# HIGHSPEED_v0_NM.net
KiCad netlist of a schematic drawn in Altium Designer
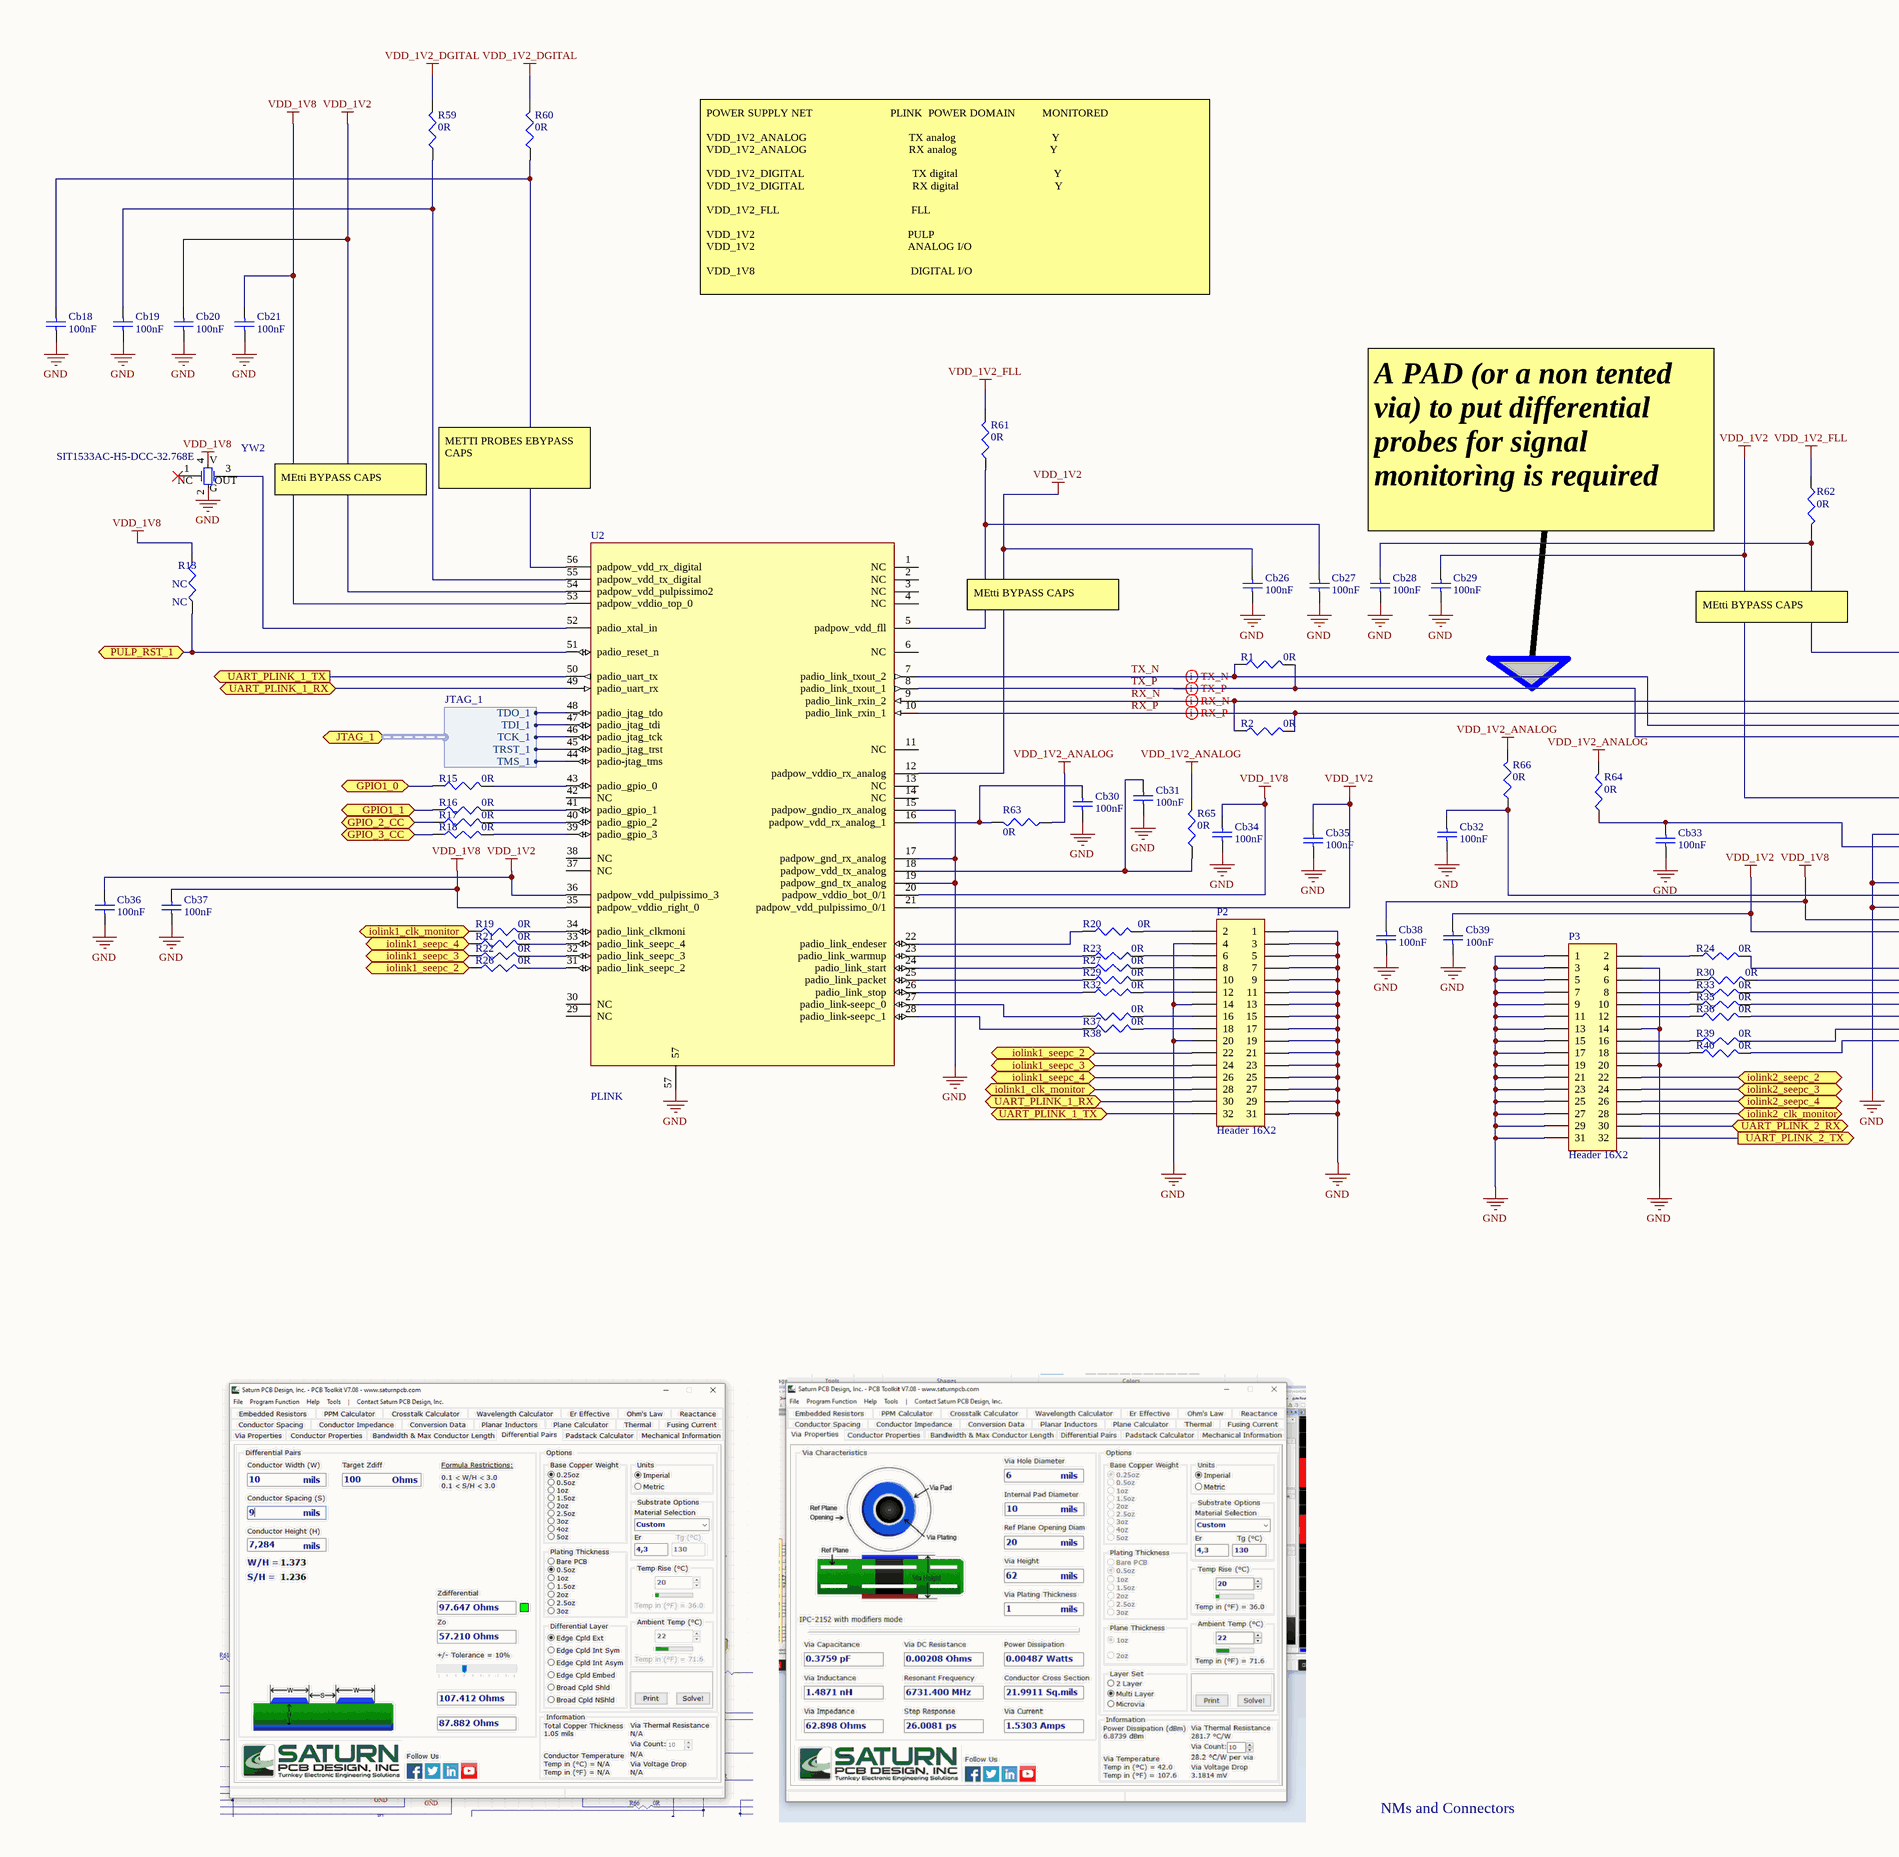
[diagram p0: HIGHSPEED_v0_NM.SchDoc, left]
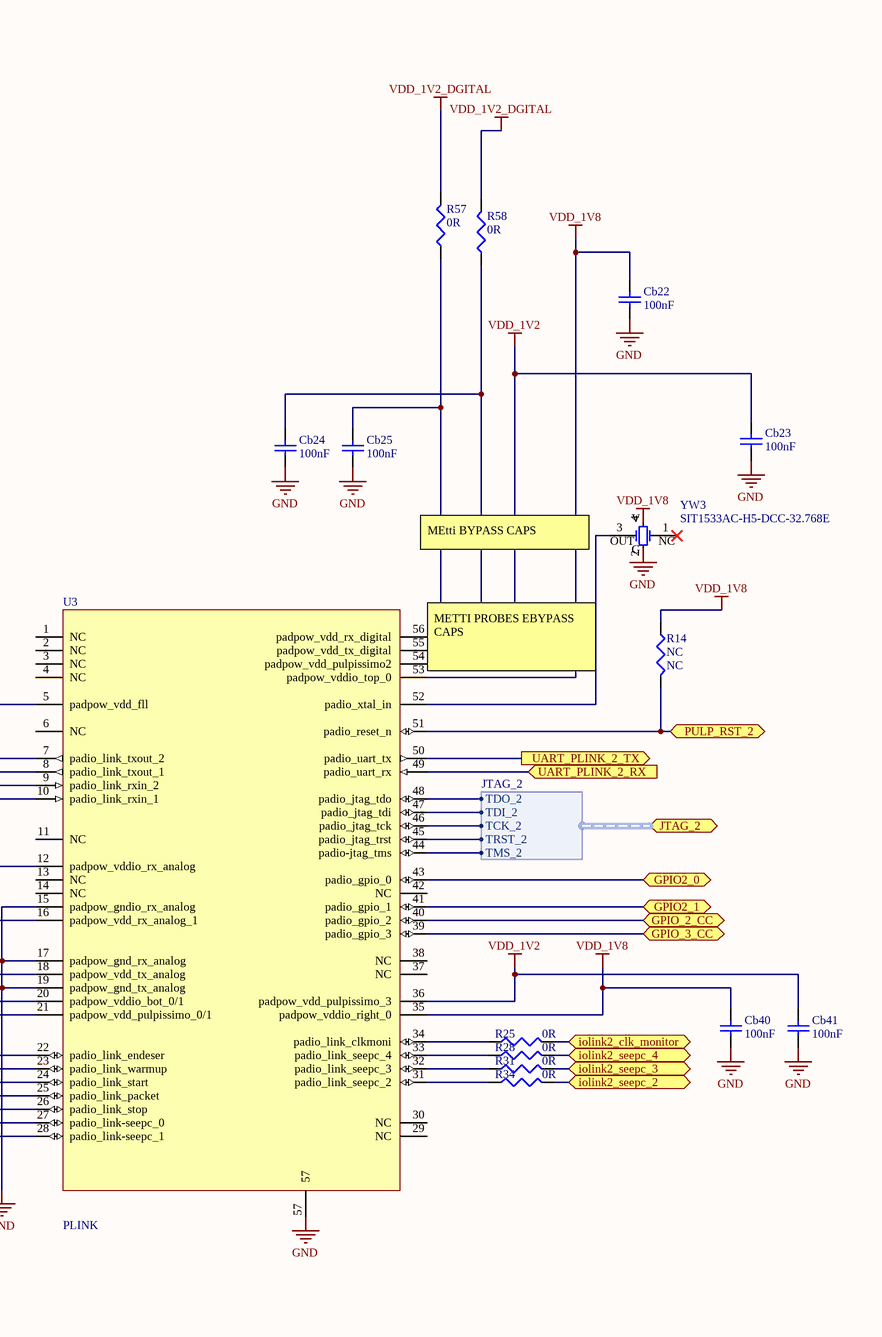
[diagram p1: HIGHSPEED_v0_NM.SchDoc, right]

(export (version "E")
  (design (tool "Eeschema 10.0.6"))
  (components
    (comp (ref "Cb18")
      (value "100nF")
      (footprint "c0603-Murata-GR")
      (description "CAP CER 22UF 10V X5R 0603")
      (fields (field (name "MANUFACTURER") "Murata") (field (name "Comment") "GRM187R61A226ME15D"))
      (libsource (lib "Custom") (part "Cap"))
    )
    (comp (ref "Cb19")
      (value "100nF")
      (footprint "c0603-Murata-GR")
      (description "CAP CER 22UF 10V X5R 0603")
      (fields (field (name "MANUFACTURER") "Murata") (field (name "Comment") "GRM187R61A226ME15D"))
      (libsource (lib "Custom") (part "Cap"))
    )
    (comp (ref "Cb20")
      (value "100nF")
      (footprint "c0603-Murata-GR")
      (description "CAP CER 22UF 10V X5R 0603")
      (fields (field (name "MANUFACTURER") "Murata") (field (name "Comment") "GRM187R61A226ME15D"))
      (libsource (lib "Custom") (part "Cap"))
    )
    (comp (ref "Cb21")
      (value "100nF")
      (footprint "c0603-Murata-GR")
      (description "CAP CER 22UF 10V X5R 0603")
      (fields (field (name "MANUFACTURER") "Murata") (field (name "Comment") "GRM187R61A226ME15D"))
      (libsource (lib "Custom") (part "Cap"))
    )
    (comp (ref "Cb22")
      (value "100nF")
      (footprint "c0603-Murata-GR")
      (description "CAP CER 22UF 10V X5R 0603")
      (fields (field (name "MANUFACTURER") "Murata") (field (name "Comment") "GRM187R61A226ME15D"))
      (libsource (lib "Custom") (part "Cap"))
    )
    (comp (ref "Cb23")
      (value "100nF")
      (footprint "c0603-Murata-GR")
      (description "CAP CER 22UF 10V X5R 0603")
      (fields (field (name "MANUFACTURER") "Murata") (field (name "Comment") "GRM187R61A226ME15D"))
      (libsource (lib "Custom") (part "Cap"))
    )
    (comp (ref "Cb24")
      (value "100nF")
      (footprint "c0603-Murata-GR")
      (description "CAP CER 22UF 10V X5R 0603")
      (fields (field (name "MANUFACTURER") "Murata") (field (name "Comment") "GRM187R61A226ME15D"))
      (libsource (lib "Custom") (part "Cap"))
    )
    (comp (ref "Cb25")
      (value "100nF")
      (footprint "c0603-Murata-GR")
      (description "CAP CER 22UF 10V X5R 0603")
      (fields (field (name "MANUFACTURER") "Murata") (field (name "Comment") "GRM187R61A226ME15D"))
      (libsource (lib "Custom") (part "Cap"))
    )
    (comp (ref "Cb26")
      (value "100nF")
      (footprint "c0603-Murata-GR")
      (description "CAP CER 22UF 10V X5R 0603")
      (fields (field (name "MANUFACTURER") "Murata") (field (name "Comment") "GRM187R61A226ME15D"))
      (libsource (lib "Custom") (part "Cap"))
    )
    (comp (ref "Cb27")
      (value "100nF")
      (footprint "c0603-Murata-GR")
      (description "CAP CER 22UF 10V X5R 0603")
      (fields (field (name "MANUFACTURER") "Murata") (field (name "Comment") "GRM187R61A226ME15D"))
      (libsource (lib "Custom") (part "Cap"))
    )
    (comp (ref "Cb28")
      (value "100nF")
      (footprint "c0603-Murata-GR")
      (description "CAP CER 22UF 10V X5R 0603")
      (fields (field (name "MANUFACTURER") "Murata") (field (name "Comment") "GRM187R61A226ME15D"))
      (libsource (lib "Custom") (part "Cap"))
    )
    (comp (ref "Cb29")
      (value "100nF")
      (footprint "c0603-Murata-GR")
      (description "CAP CER 22UF 10V X5R 0603")
      (fields (field (name "MANUFACTURER") "Murata") (field (name "Comment") "GRM187R61A226ME15D"))
      (libsource (lib "Custom") (part "Cap"))
    )
    (comp (ref "Cb30")
      (value "100nF")
      (footprint "c0603-Murata-GR")
      (description "CAP CER 22UF 10V X5R 0603")
      (fields (field (name "MANUFACTURER") "Murata") (field (name "Comment") "GRM187R61A226ME15D"))
      (libsource (lib "Custom") (part "Cap"))
    )
    (comp (ref "Cb31")
      (value "100nF")
      (footprint "c0603-Murata-GR")
      (description "CAP CER 22UF 10V X5R 0603")
      (fields (field (name "MANUFACTURER") "Murata") (field (name "Comment") "GRM187R61A226ME15D"))
      (libsource (lib "Custom") (part "Cap"))
    )
    (comp (ref "Cb32")
      (value "100nF")
      (footprint "c0603-Murata-GR")
      (description "CAP CER 22UF 10V X5R 0603")
      (fields (field (name "MANUFACTURER") "Murata") (field (name "Comment") "GRM187R61A226ME15D"))
      (libsource (lib "Custom") (part "Cap"))
    )
    (comp (ref "Cb33")
      (value "100nF")
      (footprint "c0603-Murata-GR")
      (description "CAP CER 22UF 10V X5R 0603")
      (fields (field (name "MANUFACTURER") "Murata") (field (name "Comment") "GRM187R61A226ME15D"))
      (libsource (lib "Custom") (part "Cap"))
    )
    (comp (ref "Cb34")
      (value "100nF")
      (footprint "c0603-Murata-GR")
      (description "CAP CER 22UF 10V X5R 0603")
      (fields (field (name "MANUFACTURER") "Murata") (field (name "Comment") "GRM187R61A226ME15D"))
      (libsource (lib "Custom") (part "Cap"))
    )
    (comp (ref "Cb35")
      (value "100nF")
      (footprint "c0603-Murata-GR")
      (description "CAP CER 22UF 10V X5R 0603")
      (fields (field (name "MANUFACTURER") "Murata") (field (name "Comment") "GRM187R61A226ME15D"))
      (libsource (lib "Custom") (part "Cap"))
    )
    (comp (ref "Cb36")
      (value "100nF")
      (footprint "c0603-Murata-GR")
      (description "CAP CER 22UF 10V X5R 0603")
      (fields (field (name "MANUFACTURER") "Murata") (field (name "Comment") "GRM187R61A226ME15D"))
      (libsource (lib "Custom") (part "Cap"))
    )
    (comp (ref "Cb37")
      (value "100nF")
      (footprint "c0603-Murata-GR")
      (description "CAP CER 22UF 10V X5R 0603")
      (fields (field (name "MANUFACTURER") "Murata") (field (name "Comment") "GRM187R61A226ME15D"))
      (libsource (lib "Custom") (part "Cap"))
    )
    (comp (ref "Cb38")
      (value "100nF")
      (footprint "c0603-Murata-GR")
      (description "CAP CER 22UF 10V X5R 0603")
      (fields (field (name "MANUFACTURER") "Murata") (field (name "Comment") "GRM187R61A226ME15D"))
      (libsource (lib "Custom") (part "Cap"))
    )
    (comp (ref "Cb39")
      (value "100nF")
      (footprint "c0603-Murata-GR")
      (description "CAP CER 22UF 10V X5R 0603")
      (fields (field (name "MANUFACTURER") "Murata") (field (name "Comment") "GRM187R61A226ME15D"))
      (libsource (lib "Custom") (part "Cap"))
    )
    (comp (ref "Cb40")
      (value "100nF")
      (footprint "c0603-Murata-GR")
      (description "CAP CER 22UF 10V X5R 0603")
      (fields (field (name "MANUFACTURER") "Murata") (field (name "Comment") "GRM187R61A226ME15D"))
      (libsource (lib "Custom") (part "Cap"))
    )
    (comp (ref "Cb41")
      (value "100nF")
      (footprint "c0603-Murata-GR")
      (description "CAP CER 22UF 10V X5R 0603")
      (fields (field (name "MANUFACTURER") "Murata") (field (name "Comment") "GRM187R61A226ME15D"))
      (libsource (lib "Custom") (part "Cap"))
    )
    (comp (ref "P2")
      (value "Header 16X2")
      (footprint "HDR2X16")
      (description "Header, 16-Pin, Dual row")
      (fields (field (name "PUBLISHER") "Altium Limited"))
      (libsource (lib "Miscellaneous Connectors") (part "Header 16X2"))
    )
    (comp (ref "P3")
      (value "Header 16X2")
      (footprint "HDR2X16")
      (description "Header, 16-Pin, Dual row")
      (fields (field (name "PUBLISHER") "Altium Limited"))
      (libsource (lib "") (part "Header 16X2_1"))
    )
    (comp (ref "R1")
      (value "0R")
      (footprint "J1-0603")
      (description "Resistor")
      (fields (field (name "PUBLISHER") "Altium Limited"))
      (libsource (lib "Miscellaneous Devices") (part "Res3"))
    )
    (comp (ref "R2")
      (value "0R")
      (footprint "J1-0603")
      (description "Resistor")
      (fields (field (name "PUBLISHER") "Altium Limited"))
      (libsource (lib "Miscellaneous Devices") (part "Res3"))
    )
    (comp (ref "R13")
      (value "NC")
      (footprint "0402")
      (description "Resistor")
      (fields (field (name "ALTIUM_VALUE") "NC") (field (name "PUBLISHER") "Altium Limited"))
      (libsource (lib "Miscellaneous Devices") (part "Res3"))
    )
    (comp (ref "R14")
      (value "NC")
      (footprint "0402")
      (description "Resistor")
      (fields (field (name "ALTIUM_VALUE") "NC") (field (name "PUBLISHER") "Altium Limited"))
      (libsource (lib "Miscellaneous Devices") (part "Res3"))
    )
    (comp (ref "R15")
      (value "0R")
      (footprint "0402")
      (description "Resistor")
      (fields (field (name "PUBLISHER") "Altium Limited"))
      (libsource (lib "Miscellaneous Devices") (part "Res3"))
    )
    (comp (ref "R16")
      (value "0R")
      (footprint "0402")
      (description "Resistor")
      (fields (field (name "PUBLISHER") "Altium Limited"))
      (libsource (lib "Miscellaneous Devices") (part "Res3"))
    )
    (comp (ref "R17")
      (value "0R")
      (footprint "0402")
      (description "Resistor")
      (fields (field (name "PUBLISHER") "Altium Limited"))
      (libsource (lib "Miscellaneous Devices") (part "Res3"))
    )
    (comp (ref "R18")
      (value "0R")
      (footprint "0402")
      (description "Resistor")
      (fields (field (name "PUBLISHER") "Altium Limited"))
      (libsource (lib "Miscellaneous Devices") (part "Res3"))
    )
    (comp (ref "R19")
      (value "0R")
      (footprint "0402")
      (description "Resistor")
      (fields (field (name "PUBLISHER") "Altium Limited"))
      (libsource (lib "Miscellaneous Devices") (part "Res3"))
    )
    (comp (ref "R20")
      (value "0R")
      (footprint "0402")
      (description "Resistor")
      (fields (field (name "PUBLISHER") "Altium Limited"))
      (libsource (lib "Miscellaneous Devices") (part "Res3"))
    )
    (comp (ref "R21")
      (value "0R")
      (footprint "0402")
      (description "Resistor")
      (fields (field (name "PUBLISHER") "Altium Limited"))
      (libsource (lib "Miscellaneous Devices") (part "Res3"))
    )
    (comp (ref "R22")
      (value "0R")
      (footprint "0402")
      (description "Resistor")
      (fields (field (name "PUBLISHER") "Altium Limited"))
      (libsource (lib "Miscellaneous Devices") (part "Res3"))
    )
    (comp (ref "R23")
      (value "0R")
      (footprint "0402")
      (description "Resistor")
      (fields (field (name "PUBLISHER") "Altium Limited"))
      (libsource (lib "Miscellaneous Devices") (part "Res3"))
    )
    (comp (ref "R24")
      (value "0R")
      (footprint "0402")
      (description "Resistor")
      (fields (field (name "PUBLISHER") "Altium Limited"))
      (libsource (lib "Miscellaneous Devices") (part "Res3"))
    )
    (comp (ref "R25")
      (value "0R")
      (footprint "0402")
      (description "Resistor")
      (fields (field (name "PUBLISHER") "Altium Limited"))
      (libsource (lib "Miscellaneous Devices") (part "Res3"))
    )
    (comp (ref "R26")
      (value "0R")
      (footprint "0402")
      (description "Resistor")
      (fields (field (name "PUBLISHER") "Altium Limited"))
      (libsource (lib "Miscellaneous Devices") (part "Res3"))
    )
    (comp (ref "R27")
      (value "0R")
      (footprint "0402")
      (description "Resistor")
      (fields (field (name "PUBLISHER") "Altium Limited"))
      (libsource (lib "Miscellaneous Devices") (part "Res3"))
    )
    (comp (ref "R28")
      (value "0R")
      (footprint "0402")
      (description "Resistor")
      (fields (field (name "PUBLISHER") "Altium Limited"))
      (libsource (lib "Miscellaneous Devices") (part "Res3"))
    )
    (comp (ref "R29")
      (value "0R")
      (footprint "0402")
      (description "Resistor")
      (fields (field (name "PUBLISHER") "Altium Limited"))
      (libsource (lib "Miscellaneous Devices") (part "Res3"))
    )
    (comp (ref "R30")
      (value "0R")
      (footprint "0402")
      (description "Resistor")
      (fields (field (name "PUBLISHER") "Altium Limited"))
      (libsource (lib "Miscellaneous Devices") (part "Res3"))
    )
    (comp (ref "R31")
      (value "0R")
      (footprint "0402")
      (description "Resistor")
      (fields (field (name "PUBLISHER") "Altium Limited"))
      (libsource (lib "Miscellaneous Devices") (part "Res3"))
    )
    (comp (ref "R32")
      (value "0R")
      (footprint "0402")
      (description "Resistor")
      (fields (field (name "PUBLISHER") "Altium Limited"))
      (libsource (lib "Miscellaneous Devices") (part "Res3"))
    )
    (comp (ref "R33")
      (value "0R")
      (footprint "0402")
      (description "Resistor")
      (fields (field (name "PUBLISHER") "Altium Limited"))
      (libsource (lib "Miscellaneous Devices") (part "Res3"))
    )
    (comp (ref "R34")
      (value "0R")
      (footprint "0402")
      (description "Resistor")
      (fields (field (name "PUBLISHER") "Altium Limited"))
      (libsource (lib "Miscellaneous Devices") (part "Res3"))
    )
    (comp (ref "R35")
      (value "0R")
      (footprint "0402")
      (description "Resistor")
      (fields (field (name "PUBLISHER") "Altium Limited"))
      (libsource (lib "Miscellaneous Devices") (part "Res3"))
    )
    (comp (ref "R36")
      (value "0R")
      (footprint "0402")
      (description "Resistor")
      (fields (field (name "PUBLISHER") "Altium Limited"))
      (libsource (lib "Miscellaneous Devices") (part "Res3"))
    )
    (comp (ref "R37")
      (value "0R")
      (footprint "0402")
      (description "Resistor")
      (fields (field (name "PUBLISHER") "Altium Limited"))
      (libsource (lib "Miscellaneous Devices") (part "Res3"))
    )
    (comp (ref "R38")
      (value "0R")
      (footprint "0402")
      (description "Resistor")
      (fields (field (name "PUBLISHER") "Altium Limited"))
      (libsource (lib "Miscellaneous Devices") (part "Res3"))
    )
    (comp (ref "R39")
      (value "0R")
      (footprint "0402")
      (description "Resistor")
      (fields (field (name "PUBLISHER") "Altium Limited"))
      (libsource (lib "Miscellaneous Devices") (part "Res3"))
    )
    (comp (ref "R40")
      (value "0R")
      (footprint "0402")
      (description "Resistor")
      (fields (field (name "PUBLISHER") "Altium Limited"))
      (libsource (lib "Miscellaneous Devices") (part "Res3"))
    )
    (comp (ref "R57")
      (value "0R")
      (footprint "C1206")
      (description "Resistor")
      (fields (field (name "PUBLISHER") "Altium Limited"))
      (libsource (lib "Miscellaneous Devices") (part "Res3"))
    )
    (comp (ref "R58")
      (value "0R")
      (footprint "C1206")
      (description "Resistor")
      (fields (field (name "PUBLISHER") "Altium Limited"))
      (libsource (lib "Miscellaneous Devices") (part "Res3"))
    )
    (comp (ref "R59")
      (value "0R")
      (footprint "C1206")
      (description "Resistor")
      (fields (field (name "PUBLISHER") "Altium Limited"))
      (libsource (lib "Miscellaneous Devices") (part "Res3"))
    )
    (comp (ref "R60")
      (value "0R")
      (footprint "C1206")
      (description "Resistor")
      (fields (field (name "PUBLISHER") "Altium Limited"))
      (libsource (lib "Miscellaneous Devices") (part "Res3"))
    )
    (comp (ref "R61")
      (value "0R")
      (footprint "C1206")
      (description "Resistor")
      (fields (field (name "PUBLISHER") "Altium Limited"))
      (libsource (lib "Miscellaneous Devices") (part "Res3"))
    )
    (comp (ref "R62")
      (value "0R")
      (footprint "C1206")
      (description "Resistor")
      (fields (field (name "PUBLISHER") "Altium Limited"))
      (libsource (lib "Miscellaneous Devices") (part "Res3"))
    )
    (comp (ref "R63")
      (value "0R")
      (footprint "C1206")
      (description "Resistor")
      (fields (field (name "PUBLISHER") "Altium Limited"))
      (libsource (lib "Miscellaneous Devices") (part "Res3"))
    )
    (comp (ref "R64")
      (value "0R")
      (footprint "C1206")
      (description "Resistor")
      (fields (field (name "PUBLISHER") "Altium Limited"))
      (libsource (lib "Miscellaneous Devices") (part "Res3"))
    )
    (comp (ref "R65")
      (value "0R")
      (footprint "C1206")
      (description "Resistor")
      (fields (field (name "PUBLISHER") "Altium Limited"))
      (libsource (lib "Miscellaneous Devices") (part "Res3"))
    )
    (comp (ref "R66")
      (value "0R")
      (footprint "C1206")
      (description "Resistor")
      (fields (field (name "PUBLISHER") "Altium Limited"))
      (libsource (lib "Miscellaneous Devices") (part "Res3"))
    )
    (comp (ref "U2") (value "PLINK") (footprint "Kosmodron:QFN56_M") (libsource (lib "") (part "PLINK_1")))
    (comp (ref "U3") (value "PLINK") (footprint "Kosmodron:QFN56_M") (libsource (lib "plink") (part "PLINK")))
    (comp (ref "YW2")
      (value "SIT1533AC-H5-DCC-32.768E")
      (footprint "SiT1533-C")
      (description "20 ppm, Ultra-Low Power 32.768 kHz Quartz XTAL Replacement")
      (libsource (lib "smach_lib") (part "SIT-OSC32KHZ-SIT1533AC-H5-DCC-32.768"))
    )
    (comp (ref "YW3")
      (value "SIT1533AC-H5-DCC-32.768E")
      (footprint "SiT1533-C")
      (description "20 ppm, Ultra-Low Power 32.768 kHz Quartz XTAL Replacement")
      (libsource (lib "smach_lib") (part "SIT-OSC32KHZ-SIT1533AC-H5-DCC-32.768"))
    )
  )
  (nets
    (net (code "3") (name "/GPIO1_0") (class "Default")
      (node (ref "R15") (pin "2") (pinfunction "2_2") (pintype "passive"))
    )
    (net (code "4") (name "/GPIO1_1") (class "Default")
      (node (ref "R16") (pin "2") (pinfunction "2_2") (pintype "passive"))
    )
    (net (code "5") (name "/GPIO2_0") (class "Default")
      (node (ref "U3") (pin "43") (pinfunction "padio_gpio_0_43") (pintype "bidirectional"))
    )
    (net (code "6") (name "/GPIO2_1") (class "Default")
      (node (ref "U3") (pin "41") (pinfunction "padio_gpio_1_41") (pintype "bidirectional"))
    )
    (net (code "7") (name "/GPIO_2_CC") (class "Default")
      (node (ref "R17") (pin "2") (pinfunction "2_2") (pintype "passive"))
      (node (ref "U3") (pin "40") (pinfunction "padio_gpio_2_40") (pintype "bidirectional"))
    )
    (net (code "8") (name "/GPIO_3_CC") (class "Default")
      (node (ref "R18") (pin "2") (pinfunction "2_2") (pintype "passive"))
      (node (ref "U3") (pin "39") (pinfunction "padio_gpio_3_39") (pintype "bidirectional"))
    )
    (net (code "9") (name "/PULP_RST_1") (class "Default")
      (node (ref "R13") (pin "1") (pinfunction "1_1") (pintype "passive"))
      (node (ref "U2") (pin "51") (pinfunction "padio_reset_n_51") (pintype "bidirectional"))
    )
    (net (code "10") (name "/PULP_RST_2") (class "Default")
      (node (ref "R14") (pin "1") (pinfunction "1_1") (pintype "passive"))
      (node (ref "U3") (pin "51") (pinfunction "padio_reset_n_51") (pintype "bidirectional"))
    )
    (net (code "11") (name "/RX_N") (class "Default")
      (node (ref "R2") (pin "2") (pinfunction "2_2") (pintype "passive"))
      (node (ref "U2") (pin "9") (pinfunction "padio_link_rxin_2_9") (pintype "input"))
      (node (ref "U3") (pin "7") (pinfunction "padio_link_txout_2_7") (pintype "output"))
    )
    (net (code "12") (name "/RX_P") (class "Default")
      (node (ref "R2") (pin "1") (pinfunction "1_1") (pintype "passive"))
      (node (ref "U2") (pin "10") (pinfunction "padio_link_rxin_1_10") (pintype "input"))
      (node (ref "U3") (pin "8") (pinfunction "padio_link_txout_1_8") (pintype "output"))
    )
    (net (code "13") (name "/TCK_1") (class "Default")
      (node (ref "U2") (pin "46") (pinfunction "padio_jtag_tck_46") (pintype "bidirectional"))
    )
    (net (code "14") (name "/TCK_2") (class "Default")
      (node (ref "U3") (pin "46") (pinfunction "padio_jtag_tck_46") (pintype "bidirectional"))
    )
    (net (code "15") (name "/TDI_1") (class "Default")
      (node (ref "U2") (pin "47") (pinfunction "padio_jtag_tdi_47") (pintype "bidirectional"))
    )
    (net (code "16") (name "/TDI_2") (class "Default")
      (node (ref "U3") (pin "47") (pinfunction "padio_jtag_tdi_47") (pintype "bidirectional"))
    )
    (net (code "17") (name "/TDO_1") (class "Default")
      (node (ref "U2") (pin "48") (pinfunction "padio_jtag_tdo_48") (pintype "bidirectional"))
    )
    (net (code "18") (name "/TDO_2") (class "Default")
      (node (ref "U3") (pin "48") (pinfunction "padio_jtag_tdo_48") (pintype "bidirectional"))
    )
    (net (code "19") (name "/TMS_1") (class "Default")
      (node (ref "U2") (pin "44") (pinfunction "padio-jtag_tms_44") (pintype "bidirectional"))
    )
    (net (code "20") (name "/TMS_2") (class "Default")
      (node (ref "U3") (pin "44") (pinfunction "padio-jtag_tms_44") (pintype "bidirectional"))
    )
    (net (code "21") (name "/TRST_1") (class "Default")
      (node (ref "U2") (pin "45") (pinfunction "padio_jtag_trst_45") (pintype "bidirectional"))
    )
    (net (code "22") (name "/TRST_2") (class "Default")
      (node (ref "U3") (pin "45") (pinfunction "padio_jtag_trst_45") (pintype "bidirectional"))
    )
    (net (code "23") (name "/TX_N") (class "Default")
      (node (ref "R1") (pin "2") (pinfunction "2_2") (pintype "passive"))
      (node (ref "U2") (pin "7") (pinfunction "padio_link_txout_2_7") (pintype "output"))
      (node (ref "U3") (pin "9") (pinfunction "padio_link_rxin_2_9") (pintype "input"))
    )
    (net (code "24") (name "/TX_P") (class "Default")
      (node (ref "R1") (pin "1") (pinfunction "1_1") (pintype "passive"))
      (node (ref "U2") (pin "8") (pinfunction "padio_link_txout_1_8") (pintype "output"))
      (node (ref "U3") (pin "10") (pinfunction "padio_link_rxin_1_10") (pintype "input"))
    )
    (net (code "25") (name "/UART_PLINK_1_RX") (class "Default")
      (node (ref "P2") (pin "30") (pinfunction "30_30") (pintype "passive"))
      (node (ref "U2") (pin "49") (pinfunction "padio_uart_rx_49") (pintype "input"))
    )
    (net (code "26") (name "/UART_PLINK_1_TX") (class "Default")
      (node (ref "P2") (pin "32") (pinfunction "32_32") (pintype "passive"))
      (node (ref "U2") (pin "50") (pinfunction "padio_uart_tx_50") (pintype "output"))
    )
    (net (code "27") (name "/UART_PLINK_2_RX") (class "Default")
      (node (ref "P3") (pin "30") (pinfunction "30_30") (pintype "passive"))
      (node (ref "U3") (pin "49") (pinfunction "padio_uart_rx_49") (pintype "input"))
    )
    (net (code "28") (name "/UART_PLINK_2_TX") (class "Default")
      (node (ref "P3") (pin "32") (pinfunction "32_32") (pintype "passive"))
      (node (ref "U3") (pin "50") (pinfunction "padio_uart_tx_50") (pintype "output"))
    )
    (net (code "29") (name "/iolink1_clk_monitor") (class "Default")
      (node (ref "P2") (pin "28") (pinfunction "28_28") (pintype "passive"))
      (node (ref "R19") (pin "2") (pinfunction "2_2") (pintype "passive"))
    )
    (net (code "30") (name "/iolink1_seepc_2") (class "Default")
      (node (ref "P2") (pin "22") (pinfunction "22_22") (pintype "passive"))
      (node (ref "R26") (pin "2") (pinfunction "2_2") (pintype "passive"))
    )
    (net (code "31") (name "/iolink1_seepc_3") (class "Default")
      (node (ref "P2") (pin "24") (pinfunction "24_24") (pintype "passive"))
      (node (ref "R22") (pin "2") (pinfunction "2_2") (pintype "passive"))
    )
    (net (code "32") (name "/iolink1_seepc_4") (class "Default")
      (node (ref "P2") (pin "26") (pinfunction "26_26") (pintype "passive"))
      (node (ref "R21") (pin "2") (pinfunction "2_2") (pintype "passive"))
    )
    (net (code "33") (name "/iolink2_clk_monitor") (class "Default")
      (node (ref "P3") (pin "28") (pinfunction "28_28") (pintype "passive"))
      (node (ref "R25") (pin "1") (pinfunction "1_1") (pintype "passive"))
    )
    (net (code "34") (name "/iolink2_seepc_2") (class "Default")
      (node (ref "P3") (pin "22") (pinfunction "22_22") (pintype "passive"))
      (node (ref "R34") (pin "1") (pinfunction "1_1") (pintype "passive"))
    )
    (net (code "35") (name "/iolink2_seepc_3") (class "Default")
      (node (ref "P3") (pin "24") (pinfunction "24_24") (pintype "passive"))
      (node (ref "R31") (pin "1") (pinfunction "1_1") (pintype "passive"))
    )
    (net (code "36") (name "/iolink2_seepc_4") (class "Default")
      (node (ref "P3") (pin "26") (pinfunction "26_26") (pintype "passive"))
      (node (ref "R28") (pin "1") (pinfunction "1_1") (pintype "passive"))
    )
    (net (code "39") (name "GND") (class "Default")
      (node (ref "Cb18") (pin "1") (pinfunction "1_1") (pintype "passive"))
      (node (ref "Cb19") (pin "1") (pinfunction "1_1") (pintype "passive"))
      (node (ref "Cb20") (pin "1") (pinfunction "1_1") (pintype "passive"))
      (node (ref "Cb21") (pin "1") (pinfunction "1_1") (pintype "passive"))
      (node (ref "Cb22") (pin "1") (pinfunction "1_1") (pintype "passive"))
      (node (ref "Cb23") (pin "1") (pinfunction "1_1") (pintype "passive"))
      (node (ref "Cb24") (pin "1") (pinfunction "1_1") (pintype "passive"))
      (node (ref "Cb25") (pin "1") (pinfunction "1_1") (pintype "passive"))
      (node (ref "Cb26") (pin "1") (pinfunction "1_1") (pintype "passive"))
      (node (ref "Cb27") (pin "1") (pinfunction "1_1") (pintype "passive"))
      (node (ref "Cb28") (pin "1") (pinfunction "1_1") (pintype "passive"))
      (node (ref "Cb29") (pin "1") (pinfunction "1_1") (pintype "passive"))
      (node (ref "Cb30") (pin "1") (pinfunction "1_1") (pintype "passive"))
      (node (ref "Cb31") (pin "1") (pinfunction "1_1") (pintype "passive"))
      (node (ref "Cb32") (pin "1") (pinfunction "1_1") (pintype "passive"))
      (node (ref "Cb33") (pin "1") (pinfunction "1_1") (pintype "passive"))
      (node (ref "Cb34") (pin "1") (pinfunction "1_1") (pintype "passive"))
      (node (ref "Cb35") (pin "1") (pinfunction "1_1") (pintype "passive"))
      (node (ref "Cb36") (pin "1") (pinfunction "1_1") (pintype "passive"))
      (node (ref "Cb37") (pin "1") (pinfunction "1_1") (pintype "passive"))
      (node (ref "Cb38") (pin "1") (pinfunction "1_1") (pintype "passive"))
      (node (ref "Cb39") (pin "1") (pinfunction "1_1") (pintype "passive"))
      (node (ref "Cb40") (pin "1") (pinfunction "1_1") (pintype "passive"))
      (node (ref "Cb41") (pin "1") (pinfunction "1_1") (pintype "passive"))
      (node (ref "P2") (pin "1") (pinfunction "1_1") (pintype "passive"))
      (node (ref "P2") (pin "11") (pinfunction "11_11") (pintype "passive"))
      (node (ref "P2") (pin "13") (pinfunction "13_13") (pintype "passive"))
      (node (ref "P2") (pin "14") (pinfunction "14_14") (pintype "passive"))
      (node (ref "P2") (pin "15") (pinfunction "15_15") (pintype "passive"))
      (node (ref "P2") (pin "17") (pinfunction "17_17") (pintype "passive"))
      (node (ref "P2") (pin "19") (pinfunction "19_19") (pintype "passive"))
      (node (ref "P2") (pin "20") (pinfunction "20_20") (pintype "passive"))
      (node (ref "P2") (pin "21") (pinfunction "21_21") (pintype "passive"))
      (node (ref "P2") (pin "23") (pinfunction "23_23") (pintype "passive"))
      (node (ref "P2") (pin "25") (pinfunction "25_25") (pintype "passive"))
      (node (ref "P2") (pin "27") (pinfunction "27_27") (pintype "passive"))
      (node (ref "P2") (pin "29") (pinfunction "29_29") (pintype "passive"))
      (node (ref "P2") (pin "3") (pinfunction "3_3") (pintype "passive"))
      (node (ref "P2") (pin "31") (pinfunction "31_31") (pintype "passive"))
      (node (ref "P2") (pin "4") (pinfunction "4_4") (pintype "passive"))
      (node (ref "P2") (pin "5") (pinfunction "5_5") (pintype "passive"))
      (node (ref "P2") (pin "7") (pinfunction "7_7") (pintype "passive"))
      (node (ref "P2") (pin "9") (pinfunction "9_9") (pintype "passive"))
      (node (ref "P3") (pin "1") (pinfunction "1_1") (pintype "passive"))
      (node (ref "P3") (pin "11") (pinfunction "11_11") (pintype "passive"))
      (node (ref "P3") (pin "13") (pinfunction "13_13") (pintype "passive"))
      (node (ref "P3") (pin "14") (pinfunction "14_14") (pintype "passive"))
      (node (ref "P3") (pin "15") (pinfunction "15_15") (pintype "passive"))
      (node (ref "P3") (pin "17") (pinfunction "17_17") (pintype "passive"))
      (node (ref "P3") (pin "19") (pinfunction "19_19") (pintype "passive"))
      (node (ref "P3") (pin "20") (pinfunction "20_20") (pintype "passive"))
      (node (ref "P3") (pin "21") (pinfunction "21_21") (pintype "passive"))
      (node (ref "P3") (pin "23") (pinfunction "23_23") (pintype "passive"))
      (node (ref "P3") (pin "25") (pinfunction "25_25") (pintype "passive"))
      (node (ref "P3") (pin "27") (pinfunction "27_27") (pintype "passive"))
      (node (ref "P3") (pin "29") (pinfunction "29_29") (pintype "passive"))
      (node (ref "P3") (pin "3") (pinfunction "3_3") (pintype "passive"))
      (node (ref "P3") (pin "31") (pinfunction "31_31") (pintype "passive"))
      (node (ref "P3") (pin "4") (pinfunction "4_4") (pintype "passive"))
      (node (ref "P3") (pin "5") (pinfunction "5_5") (pintype "passive"))
      (node (ref "P3") (pin "7") (pinfunction "7_7") (pintype "passive"))
      (node (ref "P3") (pin "9") (pinfunction "9_9") (pintype "passive"))
      (node (ref "U2") (pin "15") (pinfunction "padpow_gndio_rx_analog_15") (pintype "power_in"))
      (node (ref "U2") (pin "17") (pinfunction "padpow_gnd_rx_analog_17") (pintype "power_in"))
      (node (ref "U2") (pin "19") (pinfunction "padpow_gnd_tx_analog_19") (pintype "power_in"))
      (node (ref "U2") (pin "57") (pinfunction "57_57") (pintype "passive"))
      (node (ref "U3") (pin "15") (pinfunction "padpow_gndio_rx_analog_15") (pintype "power_in"))
      (node (ref "U3") (pin "17") (pinfunction "padpow_gnd_rx_analog_17") (pintype "power_in"))
      (node (ref "U3") (pin "19") (pinfunction "padpow_gnd_tx_analog_19") (pintype "power_in"))
      (node (ref "U3") (pin "57") (pinfunction "57_57") (pintype "passive"))
      (node (ref "YW2") (pin "2") (pinfunction "GND_2") (pintype "power_in"))
      (node (ref "YW3") (pin "2") (pinfunction "GND_2") (pintype "power_in"))
    )
    (net (code "40") (name "Net-(P2-Pad2)") (class "Default")
      (node (ref "P2") (pin "2") (pinfunction "2_2") (pintype "passive"))
      (node (ref "R20") (pin "2") (pinfunction "2_2") (pintype "passive"))
    )
    (net (code "41") (name "Net-(P2-Pad6)") (class "Default")
      (node (ref "P2") (pin "6") (pinfunction "6_6") (pintype "passive"))
      (node (ref "R23") (pin "2") (pinfunction "2_2") (pintype "passive"))
    )
    (net (code "42") (name "Net-(P2-Pad8)") (class "Default")
      (node (ref "P2") (pin "8") (pinfunction "8_8") (pintype "passive"))
      (node (ref "R27") (pin "2") (pinfunction "2_2") (pintype "passive"))
    )
    (net (code "43") (name "Net-(P2-Pad10)") (class "Default")
      (node (ref "P2") (pin "10") (pinfunction "10_10") (pintype "passive"))
      (node (ref "R29") (pin "2") (pinfunction "2_2") (pintype "passive"))
    )
    (net (code "44") (name "Net-(P2-Pad12)") (class "Default")
      (node (ref "P2") (pin "12") (pinfunction "12_12") (pintype "passive"))
      (node (ref "R32") (pin "2") (pinfunction "2_2") (pintype "passive"))
    )
    (net (code "45") (name "Net-(P2-Pad16)") (class "Default")
      (node (ref "P2") (pin "16") (pinfunction "16_16") (pintype "passive"))
      (node (ref "R37") (pin "2") (pinfunction "2_2") (pintype "passive"))
    )
    (net (code "46") (name "Net-(P2-Pad18)") (class "Default")
      (node (ref "P2") (pin "18") (pinfunction "18_18") (pintype "passive"))
      (node (ref "R38") (pin "2") (pinfunction "2_2") (pintype "passive"))
    )
    (net (code "47") (name "Net-(P3-Pad2)") (class "Default")
      (node (ref "P3") (pin "2") (pinfunction "2_2") (pintype "passive"))
      (node (ref "R24") (pin "2") (pinfunction "2_2") (pintype "passive"))
    )
    (net (code "48") (name "Net-(P3-Pad6)") (class "Default")
      (node (ref "P3") (pin "6") (pinfunction "6_6") (pintype "passive"))
      (node (ref "R30") (pin "2") (pinfunction "2_2") (pintype "passive"))
    )
    (net (code "49") (name "Net-(P3-Pad8)") (class "Default")
      (node (ref "P3") (pin "8") (pinfunction "8_8") (pintype "passive"))
      (node (ref "R33") (pin "2") (pinfunction "2_2") (pintype "passive"))
    )
    (net (code "50") (name "Net-(P3-Pad10)") (class "Default")
      (node (ref "P3") (pin "10") (pinfunction "10_10") (pintype "passive"))
      (node (ref "R35") (pin "2") (pinfunction "2_2") (pintype "passive"))
    )
    (net (code "51") (name "Net-(P3-Pad12)") (class "Default")
      (node (ref "P3") (pin "12") (pinfunction "12_12") (pintype "passive"))
      (node (ref "R36") (pin "2") (pinfunction "2_2") (pintype "passive"))
    )
    (net (code "52") (name "Net-(P3-Pad16)") (class "Default")
      (node (ref "P3") (pin "16") (pinfunction "16_16") (pintype "passive"))
      (node (ref "R39") (pin "2") (pinfunction "2_2") (pintype "passive"))
    )
    (net (code "53") (name "Net-(P3-Pad18)") (class "Default")
      (node (ref "P3") (pin "18") (pinfunction "18_18") (pintype "passive"))
      (node (ref "R40") (pin "2") (pinfunction "2_2") (pintype "passive"))
    )
    (net (code "54") (name "Net-(U2-padio_gpio_0)") (class "Default")
      (node (ref "R15") (pin "1") (pinfunction "1_1") (pintype "passive"))
      (node (ref "U2") (pin "43") (pinfunction "padio_gpio_0_43") (pintype "bidirectional"))
    )
    (net (code "55") (name "Net-(U2-padio_gpio_1)") (class "Default")
      (node (ref "R16") (pin "1") (pinfunction "1_1") (pintype "passive"))
      (node (ref "U2") (pin "41") (pinfunction "padio_gpio_1_41") (pintype "bidirectional"))
    )
    (net (code "56") (name "Net-(U2-padio_gpio_2)") (class "Default")
      (node (ref "R17") (pin "1") (pinfunction "1_1") (pintype "passive"))
      (node (ref "U2") (pin "40") (pinfunction "padio_gpio_2_40") (pintype "bidirectional"))
    )
    (net (code "57") (name "Net-(U2-padio_gpio_3)") (class "Default")
      (node (ref "R18") (pin "1") (pinfunction "1_1") (pintype "passive"))
      (node (ref "U2") (pin "39") (pinfunction "padio_gpio_3_39") (pintype "bidirectional"))
    )
    (net (code "58") (name "Net-(U2-padio_link-seepc_0)") (class "Default")
      (node (ref "R37") (pin "1") (pinfunction "1_1") (pintype "passive"))
      (node (ref "U2") (pin "27") (pinfunction "padio_link-seepc_0_27") (pintype "bidirectional"))
    )
    (net (code "59") (name "Net-(U2-padio_link-seepc_1)") (class "Default")
      (node (ref "R38") (pin "1") (pinfunction "1_1") (pintype "passive"))
      (node (ref "U2") (pin "28") (pinfunction "padio_link-seepc_1_28") (pintype "bidirectional"))
    )
    (net (code "60") (name "Net-(U2-padio_link_clkmoni)") (class "Default")
      (node (ref "R19") (pin "1") (pinfunction "1_1") (pintype "passive"))
      (node (ref "U2") (pin "34") (pinfunction "padio_link_clkmoni_34") (pintype "bidirectional"))
    )
    (net (code "61") (name "Net-(U2-padio_link_endeser)") (class "Default")
      (node (ref "R20") (pin "1") (pinfunction "1_1") (pintype "passive"))
      (node (ref "U2") (pin "22") (pinfunction "padio_link_endeser_22") (pintype "bidirectional"))
    )
    (net (code "62") (name "Net-(U2-padio_link_packet)") (class "Default")
      (node (ref "R29") (pin "1") (pinfunction "1_1") (pintype "passive"))
      (node (ref "U2") (pin "25") (pinfunction "padio_link_packet_25") (pintype "bidirectional"))
    )
    (net (code "63") (name "Net-(U2-padio_link_seepc_2)") (class "Default")
      (node (ref "R26") (pin "1") (pinfunction "1_1") (pintype "passive"))
      (node (ref "U2") (pin "31") (pinfunction "padio_link_seepc_2_31") (pintype "bidirectional"))
    )
    (net (code "64") (name "Net-(U2-padio_link_seepc_3)") (class "Default")
      (node (ref "R22") (pin "1") (pinfunction "1_1") (pintype "passive"))
      (node (ref "U2") (pin "32") (pinfunction "padio_link_seepc_3_32") (pintype "bidirectional"))
    )
    (net (code "65") (name "Net-(U2-padio_link_seepc_4)") (class "Default")
      (node (ref "R21") (pin "1") (pinfunction "1_1") (pintype "passive"))
      (node (ref "U2") (pin "33") (pinfunction "padio_link_seepc_4_33") (pintype "bidirectional"))
    )
    (net (code "66") (name "Net-(U2-padio_link_start)") (class "Default")
      (node (ref "R27") (pin "1") (pinfunction "1_1") (pintype "passive"))
      (node (ref "U2") (pin "24") (pinfunction "padio_link_start_24") (pintype "bidirectional"))
    )
    (net (code "67") (name "Net-(U2-padio_link_stop)") (class "Default")
      (node (ref "R32") (pin "1") (pinfunction "1_1") (pintype "passive"))
      (node (ref "U2") (pin "26") (pinfunction "padio_link_stop_26") (pintype "bidirectional"))
    )
    (net (code "68") (name "Net-(U2-padio_link_warmup)") (class "Default")
      (node (ref "R23") (pin "1") (pinfunction "1_1") (pintype "passive"))
      (node (ref "U2") (pin "23") (pinfunction "padio_link_warmup_23") (pintype "bidirectional"))
    )
    (net (code "69") (name "Net-(U2-padio_xtal_in)") (class "Default")
      (node (ref "U2") (pin "52") (pinfunction "padio_xtal_in_52") (pintype "passive"))
      (node (ref "YW2") (pin "3") (pinfunction "OUT_3") (pintype "passive"))
    )
    (net (code "70") (name "Net-(U2-padpow_vdd_fll)") (class "Default")
      (node (ref "Cb27") (pin "2") (pinfunction "2_2") (pintype "passive"))
      (node (ref "R61") (pin "2") (pinfunction "2_2") (pintype "passive"))
      (node (ref "U2") (pin "5") (pinfunction "padpow_vdd_fll_5") (pintype "power_in"))
    )
    (net (code "71") (name "Net-(U2-padpow_vdd_rx_analog_1)") (class "Default")
      (node (ref "Cb30") (pin "2") (pinfunction "2_2") (pintype "passive"))
      (node (ref "R63") (pin "1") (pinfunction "1_1") (pintype "passive"))
      (node (ref "U2") (pin "16") (pinfunction "padpow_vdd_rx_analog_1_16") (pintype "power_in"))
    )
    (net (code "72") (name "Net-(U2-padpow_vdd_rx_digital)") (class "Default")
      (node (ref "Cb18") (pin "2") (pinfunction "2_2") (pintype "passive"))
      (node (ref "R60") (pin "2") (pinfunction "2_2") (pintype "passive"))
      (node (ref "U2") (pin "56") (pinfunction "padpow_vdd_rx_digital_56") (pintype "passive"))
    )
    (net (code "73") (name "Net-(U2-padpow_vdd_tx_analog)") (class "Default")
      (node (ref "Cb31") (pin "2") (pinfunction "2_2") (pintype "passive"))
      (node (ref "R65") (pin "2") (pinfunction "2_2") (pintype "passive"))
      (node (ref "U2") (pin "18") (pinfunction "padpow_vdd_tx_analog_18") (pintype "power_in"))
    )
    (net (code "74") (name "Net-(U2-padpow_vdd_tx_digital)") (class "Default")
      (node (ref "Cb19") (pin "2") (pinfunction "2_2") (pintype "passive"))
      (node (ref "R59") (pin "2") (pinfunction "2_2") (pintype "passive"))
      (node (ref "U2") (pin "55") (pinfunction "padpow_vdd_tx_digital_55") (pintype "power_in"))
    )
    (net (code "75") (name "Net-(U3-padio_link-seepc_0)") (class "Default")
      (node (ref "R39") (pin "1") (pinfunction "1_1") (pintype "passive"))
      (node (ref "U3") (pin "27") (pinfunction "padio_link-seepc_0_27") (pintype "bidirectional"))
    )
    (net (code "76") (name "Net-(U3-padio_link-seepc_1)") (class "Default")
      (node (ref "R40") (pin "1") (pinfunction "1_1") (pintype "passive"))
      (node (ref "U3") (pin "28") (pinfunction "padio_link-seepc_1_28") (pintype "bidirectional"))
    )
    (net (code "77") (name "Net-(U3-padio_link_clkmoni)") (class "Default")
      (node (ref "R25") (pin "2") (pinfunction "2_2") (pintype "passive"))
      (node (ref "U3") (pin "34") (pinfunction "padio_link_clkmoni_34") (pintype "bidirectional"))
    )
    (net (code "78") (name "Net-(U3-padio_link_endeser)") (class "Default")
      (node (ref "R24") (pin "1") (pinfunction "1_1") (pintype "passive"))
      (node (ref "U3") (pin "22") (pinfunction "padio_link_endeser_22") (pintype "bidirectional"))
    )
    (net (code "79") (name "Net-(U3-padio_link_packet)") (class "Default")
      (node (ref "R35") (pin "1") (pinfunction "1_1") (pintype "passive"))
      (node (ref "U3") (pin "25") (pinfunction "padio_link_packet_25") (pintype "bidirectional"))
    )
    (net (code "80") (name "Net-(U3-padio_link_seepc_2)") (class "Default")
      (node (ref "R34") (pin "2") (pinfunction "2_2") (pintype "passive"))
      (node (ref "U3") (pin "31") (pinfunction "padio_link_seepc_2_31") (pintype "bidirectional"))
    )
    (net (code "81") (name "Net-(U3-padio_link_seepc_3)") (class "Default")
      (node (ref "R31") (pin "2") (pinfunction "2_2") (pintype "passive"))
      (node (ref "U3") (pin "32") (pinfunction "padio_link_seepc_3_32") (pintype "bidirectional"))
    )
    (net (code "82") (name "Net-(U3-padio_link_seepc_4)") (class "Default")
      (node (ref "R28") (pin "2") (pinfunction "2_2") (pintype "passive"))
      (node (ref "U3") (pin "33") (pinfunction "padio_link_seepc_4_33") (pintype "bidirectional"))
    )
    (net (code "83") (name "Net-(U3-padio_link_start)") (class "Default")
      (node (ref "R33") (pin "1") (pinfunction "1_1") (pintype "passive"))
      (node (ref "U3") (pin "24") (pinfunction "padio_link_start_24") (pintype "bidirectional"))
    )
    (net (code "84") (name "Net-(U3-padio_link_stop)") (class "Default")
      (node (ref "R36") (pin "1") (pinfunction "1_1") (pintype "passive"))
      (node (ref "U3") (pin "26") (pinfunction "padio_link_stop_26") (pintype "bidirectional"))
    )
    (net (code "85") (name "Net-(U3-padio_link_warmup)") (class "Default")
      (node (ref "R30") (pin "1") (pinfunction "1_1") (pintype "passive"))
      (node (ref "U3") (pin "23") (pinfunction "padio_link_warmup_23") (pintype "bidirectional"))
    )
    (net (code "86") (name "Net-(U3-padio_xtal_in)") (class "Default")
      (node (ref "U3") (pin "52") (pinfunction "padio_xtal_in_52") (pintype "passive"))
      (node (ref "YW3") (pin "3") (pinfunction "OUT_3") (pintype "passive"))
    )
    (net (code "87") (name "Net-(U3-padpow_vdd_fll)") (class "Default")
      (node (ref "Cb28") (pin "2") (pinfunction "2_2") (pintype "passive"))
      (node (ref "R62") (pin "1") (pinfunction "1_1") (pintype "passive"))
      (node (ref "U3") (pin "5") (pinfunction "padpow_vdd_fll_5") (pintype "power_in"))
    )
    (net (code "88") (name "Net-(U3-padpow_vdd_rx_analog_1)") (class "Default")
      (node (ref "Cb33") (pin "2") (pinfunction "2_2") (pintype "passive"))
      (node (ref "R64") (pin "2") (pinfunction "2_2") (pintype "passive"))
      (node (ref "U3") (pin "16") (pinfunction "padpow_vdd_rx_analog_1_16") (pintype "power_in"))
    )
    (net (code "89") (name "Net-(U3-padpow_vdd_rx_digital)") (class "Default")
      (node (ref "Cb25") (pin "2") (pinfunction "2_2") (pintype "passive"))
      (node (ref "R57") (pin "2") (pinfunction "2_2") (pintype "passive"))
      (node (ref "U3") (pin "56") (pinfunction "padpow_vdd_rx_digital_56") (pintype "passive"))
    )
    (net (code "90") (name "Net-(U3-padpow_vdd_tx_analog)") (class "Default")
      (node (ref "Cb32") (pin "2") (pinfunction "2_2") (pintype "passive"))
      (node (ref "R66") (pin "2") (pinfunction "2_2") (pintype "passive"))
      (node (ref "U3") (pin "18") (pinfunction "padpow_vdd_tx_analog_18") (pintype "power_in"))
    )
    (net (code "91") (name "Net-(U3-padpow_vdd_tx_digital)") (class "Default")
      (node (ref "Cb24") (pin "2") (pinfunction "2_2") (pintype "passive"))
      (node (ref "R58") (pin "2") (pinfunction "2_2") (pintype "passive"))
      (node (ref "U3") (pin "55") (pinfunction "padpow_vdd_tx_digital_55") (pintype "power_in"))
    )
    (net (code "92") (name "VDD_1V2") (class "Default")
      (node (ref "Cb20") (pin "2") (pinfunction "2_2") (pintype "passive"))
      (node (ref "Cb23") (pin "2") (pinfunction "2_2") (pintype "passive"))
      (node (ref "Cb26") (pin "2") (pinfunction "2_2") (pintype "passive"))
      (node (ref "Cb29") (pin "2") (pinfunction "2_2") (pintype "passive"))
      (node (ref "Cb35") (pin "2") (pinfunction "2_2") (pintype "passive"))
      (node (ref "Cb36") (pin "2") (pinfunction "2_2") (pintype "passive"))
      (node (ref "Cb39") (pin "2") (pinfunction "2_2") (pintype "passive"))
      (node (ref "Cb41") (pin "2") (pinfunction "2_2") (pintype "passive"))
      (node (ref "U2") (pin "12") (pinfunction "padpow_vddio_rx_analog_12") (pintype "power_in"))
      (node (ref "U2") (pin "21") (pinfunction "padpow_vdd_pulpissimo_0/1_21") (pintype "power_in"))
      (node (ref "U2") (pin "36") (pinfunction "padpow_vdd_pulpissimo_3_36") (pintype "power_in"))
      (node (ref "U2") (pin "54") (pinfunction "padpow_vdd_pulpissimo2_54") (pintype "power_in"))
      (node (ref "U3") (pin "12") (pinfunction "padpow_vddio_rx_analog_12") (pintype "power_in"))
      (node (ref "U3") (pin "21") (pinfunction "padpow_vdd_pulpissimo_0/1_21") (pintype "power_in"))
      (node (ref "U3") (pin "36") (pinfunction "padpow_vdd_pulpissimo_3_36") (pintype "power_in"))
      (node (ref "U3") (pin "54") (pinfunction "padpow_vdd_pulpissimo2_54") (pintype "power_in"))
    )
    (net (code "93") (name "VDD_1V2_ANALOG") (class "Default")
      (node (ref "R63") (pin "2") (pinfunction "2_2") (pintype "passive"))
      (node (ref "R64") (pin "1") (pinfunction "1_1") (pintype "passive"))
      (node (ref "R65") (pin "1") (pinfunction "1_1") (pintype "passive"))
      (node (ref "R66") (pin "1") (pinfunction "1_1") (pintype "passive"))
    )
    (net (code "94") (name "VDD_1V2_DGITAL") (class "Default")
      (node (ref "R57") (pin "1") (pinfunction "1_1") (pintype "passive"))
      (node (ref "R58") (pin "1") (pinfunction "1_1") (pintype "passive"))
      (node (ref "R59") (pin "1") (pinfunction "1_1") (pintype "passive"))
      (node (ref "R60") (pin "1") (pinfunction "1_1") (pintype "passive"))
    )
    (net (code "95") (name "VDD_1V2_FLL") (class "Default")
      (node (ref "R61") (pin "1") (pinfunction "1_1") (pintype "passive"))
      (node (ref "R62") (pin "2") (pinfunction "2_2") (pintype "passive"))
    )
    (net (code "96") (name "VDD_1V8") (class "Default")
      (node (ref "Cb21") (pin "2") (pinfunction "2_2") (pintype "passive"))
      (node (ref "Cb22") (pin "2") (pinfunction "2_2") (pintype "passive"))
      (node (ref "Cb34") (pin "2") (pinfunction "2_2") (pintype "passive"))
      (node (ref "Cb37") (pin "2") (pinfunction "2_2") (pintype "passive"))
      (node (ref "Cb38") (pin "2") (pinfunction "2_2") (pintype "passive"))
      (node (ref "Cb40") (pin "2") (pinfunction "2_2") (pintype "passive"))
      (node (ref "R13") (pin "2") (pinfunction "2_2") (pintype "passive"))
      (node (ref "R14") (pin "2") (pinfunction "2_2") (pintype "passive"))
      (node (ref "U2") (pin "20") (pinfunction "padpow_vddio_bot_0/1_20") (pintype "passive"))
      (node (ref "U2") (pin "35") (pinfunction "padpow_vddio_right_0_35") (pintype "power_in"))
      (node (ref "U2") (pin "53") (pinfunction "padpow_vddio_top_0_53") (pintype "power_in"))
      (node (ref "U3") (pin "20") (pinfunction "padpow_vddio_bot_0/1_20") (pintype "passive"))
      (node (ref "U3") (pin "35") (pinfunction "padpow_vddio_right_0_35") (pintype "power_in"))
      (node (ref "U3") (pin "53") (pinfunction "padpow_vddio_top_0_53") (pintype "power_in"))
      (node (ref "YW2") (pin "4") (pinfunction "VDD_4") (pintype "power_in"))
      (node (ref "YW3") (pin "4") (pinfunction "VDD_4") (pintype "power_in"))
    )
    (net (code "97") (name "unconnected-(U2-NC-Pad1)") (class "Default")
      (node (ref "U2") (pin "1") (pinfunction "NC_1") (pintype "passive"))
    )
    (net (code "98") (name "unconnected-(U2-NC-Pad2)") (class "Default")
      (node (ref "U2") (pin "2") (pinfunction "NC_2") (pintype "passive"))
    )
    (net (code "99") (name "unconnected-(U2-NC-Pad3)") (class "Default")
      (node (ref "U2") (pin "3") (pinfunction "NC_3") (pintype "passive"))
    )
    (net (code "100") (name "unconnected-(U2-NC-Pad4)") (class "Default")
      (node (ref "U2") (pin "4") (pinfunction "NC_4") (pintype "passive"))
    )
    (net (code "101") (name "unconnected-(U2-NC-Pad6)") (class "Default")
      (node (ref "U2") (pin "6") (pinfunction "NC_6") (pintype "passive"))
    )
    (net (code "102") (name "unconnected-(U2-NC-Pad11)") (class "Default")
      (node (ref "U2") (pin "11") (pinfunction "NC_11") (pintype "passive"))
    )
    (net (code "103") (name "unconnected-(U2-NC-Pad13)") (class "Default")
      (node (ref "U2") (pin "13") (pinfunction "NC_13") (pintype "passive"))
    )
    (net (code "104") (name "unconnected-(U2-NC-Pad14)") (class "Default")
      (node (ref "U2") (pin "14") (pinfunction "NC_14") (pintype "passive"))
    )
    (net (code "105") (name "unconnected-(U2-NC-Pad29)") (class "Default")
      (node (ref "U2") (pin "29") (pinfunction "NC_29") (pintype "passive"))
    )
    (net (code "106") (name "unconnected-(U2-NC-Pad30)") (class "Default")
      (node (ref "U2") (pin "30") (pinfunction "NC_30") (pintype "passive"))
    )
    (net (code "107") (name "unconnected-(U2-NC-Pad37)") (class "Default")
      (node (ref "U2") (pin "37") (pinfunction "NC_37") (pintype "passive"))
    )
    (net (code "108") (name "unconnected-(U2-NC-Pad38)") (class "Default")
      (node (ref "U2") (pin "38") (pinfunction "NC_38") (pintype "passive"))
    )
    (net (code "109") (name "unconnected-(U2-NC-Pad42)") (class "Default")
      (node (ref "U2") (pin "42") (pinfunction "NC_42") (pintype "passive"))
    )
    (net (code "110") (name "unconnected-(U3-NC-Pad1)") (class "Default")
      (node (ref "U3") (pin "1") (pinfunction "NC_1") (pintype "passive"))
    )
    (net (code "111") (name "unconnected-(U3-NC-Pad2)") (class "Default")
      (node (ref "U3") (pin "2") (pinfunction "NC_2") (pintype "passive"))
    )
    (net (code "112") (name "unconnected-(U3-NC-Pad3)") (class "Default")
      (node (ref "U3") (pin "3") (pinfunction "NC_3") (pintype "passive"))
    )
    (net (code "113") (name "unconnected-(U3-NC-Pad4)") (class "Default")
      (node (ref "U3") (pin "4") (pinfunction "NC_4") (pintype "passive"))
    )
    (net (code "114") (name "unconnected-(U3-NC-Pad6)") (class "Default")
      (node (ref "U3") (pin "6") (pinfunction "NC_6") (pintype "passive"))
    )
    (net (code "115") (name "unconnected-(U3-NC-Pad11)") (class "Default")
      (node (ref "U3") (pin "11") (pinfunction "NC_11") (pintype "passive"))
    )
    (net (code "116") (name "unconnected-(U3-NC-Pad13)") (class "Default")
      (node (ref "U3") (pin "13") (pinfunction "NC_13") (pintype "passive"))
    )
    (net (code "117") (name "unconnected-(U3-NC-Pad14)") (class "Default")
      (node (ref "U3") (pin "14") (pinfunction "NC_14") (pintype "passive"))
    )
    (net (code "118") (name "unconnected-(U3-NC-Pad29)") (class "Default")
      (node (ref "U3") (pin "29") (pinfunction "NC_29") (pintype "passive"))
    )
    (net (code "119") (name "unconnected-(U3-NC-Pad30)") (class "Default")
      (node (ref "U3") (pin "30") (pinfunction "NC_30") (pintype "passive"))
    )
    (net (code "120") (name "unconnected-(U3-NC-Pad37)") (class "Default")
      (node (ref "U3") (pin "37") (pinfunction "NC_37") (pintype "passive"))
    )
    (net (code "121") (name "unconnected-(U3-NC-Pad38)") (class "Default")
      (node (ref "U3") (pin "38") (pinfunction "NC_38") (pintype "passive"))
    )
    (net (code "122") (name "unconnected-(U3-NC-Pad42)") (class "Default")
      (node (ref "U3") (pin "42") (pinfunction "NC_42") (pintype "passive"))
    )
    (net (code "123") (name "unconnected-(YW2-NC-Pad1)") (class "Default")
      (node (ref "YW2") (pin "1") (pinfunction "NC_1") (pintype "passive+no_connect"))
    )
    (net (code "124") (name "unconnected-(YW3-NC-Pad1)") (class "Default")
      (node (ref "YW3") (pin "1") (pinfunction "NC_1") (pintype "passive+no_connect"))
    )
  )
)
